# Sheet1.net
KiCad netlist of a schematic drawn in Altium Designer
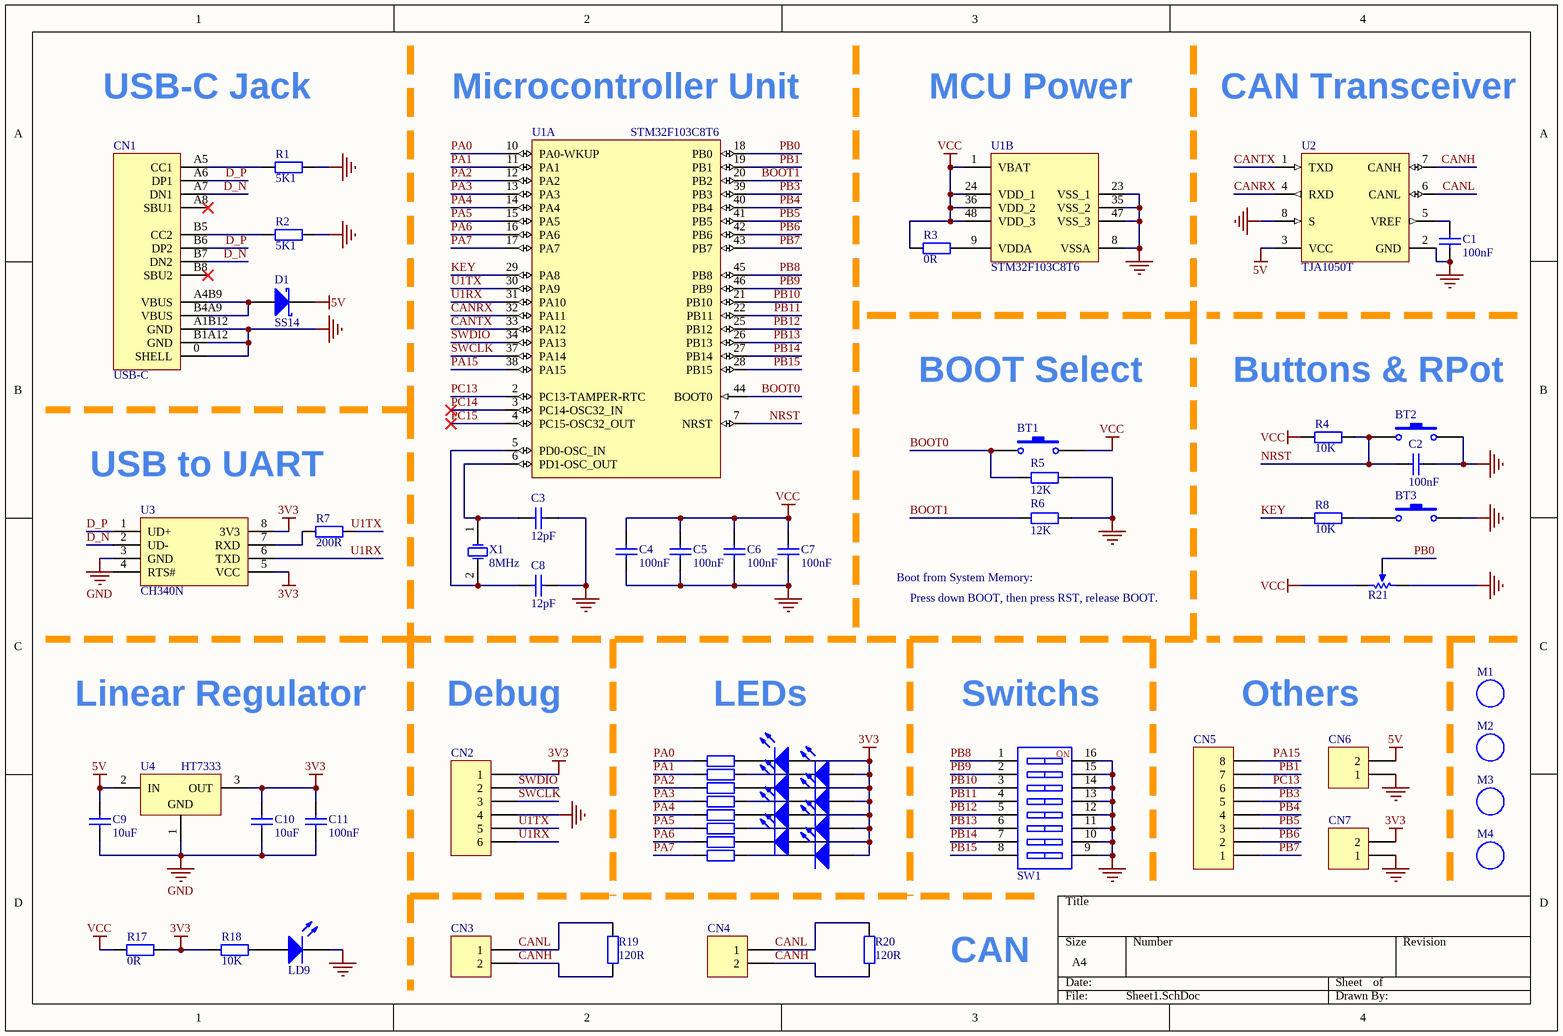
[diagram p0: Sheet1.SchDoc]

(export (version "E")
  (design (tool "Eeschema 10.0.6"))
  (components
    (comp (ref "BT1")
      (value "SW-PB")
      (footprint "TSW SMD-3*4*2.5")
      (description "Switch")
      (fields (field (name "PUBLISHER") "Altium Limited"))
      (libsource (lib "Miscellaneous Devices") (part "SW-PB"))
    )
    (comp (ref "BT2")
      (value "SW-PB")
      (footprint "TSW SMD-3*6*2.5")
      (description "Switch")
      (fields (field (name "PUBLISHER") "Altium Limited"))
      (libsource (lib "Miscellaneous Devices") (part "SW-PB"))
    )
    (comp (ref "BT3")
      (value "SW-PB")
      (footprint "TSW SMD-3*6*2.5")
      (description "Switch")
      (fields (field (name "PUBLISHER") "Altium Limited"))
      (libsource (lib "Miscellaneous Devices") (part "SW-PB"))
    )
    (comp (ref "C1")
      (value "100nF")
      (footprint "C 0603")
      (description "Capacitor")
      (fields (field (name "Comment") "Cap") (field (name "PUBLISHER") "Altium Limited"))
      (libsource (lib "Miscellaneous Devices") (part "Cap"))
    )
    (comp (ref "C2")
      (value "100nF")
      (footprint "C 0603")
      (description "Capacitor")
      (fields (field (name "Comment") "Cap") (field (name "PUBLISHER") "Altium Limited"))
      (libsource (lib "Miscellaneous Devices") (part "Cap"))
    )
    (comp (ref "C3")
      (value "12pF")
      (footprint "C 0603")
      (description "Capacitor")
      (fields (field (name "Comment") "Cap") (field (name "PUBLISHER") "Altium Limited"))
      (libsource (lib "Miscellaneous Devices") (part "Cap"))
    )
    (comp (ref "C4")
      (value "100nF")
      (footprint "C 0603")
      (description "Capacitor")
      (fields (field (name "Comment") "Cap") (field (name "PUBLISHER") "Altium Limited"))
      (libsource (lib "Miscellaneous Devices") (part "Cap"))
    )
    (comp (ref "C5")
      (value "100nF")
      (footprint "C 0603")
      (description "Capacitor")
      (fields (field (name "Comment") "Cap") (field (name "PUBLISHER") "Altium Limited"))
      (libsource (lib "Miscellaneous Devices") (part "Cap"))
    )
    (comp (ref "C6")
      (value "100nF")
      (footprint "C 0603")
      (description "Capacitor")
      (fields (field (name "Comment") "Cap") (field (name "PUBLISHER") "Altium Limited"))
      (libsource (lib "Miscellaneous Devices") (part "Cap"))
    )
    (comp (ref "C7")
      (value "100nF")
      (footprint "C 0603")
      (description "Capacitor")
      (fields (field (name "Comment") "Cap") (field (name "PUBLISHER") "Altium Limited"))
      (libsource (lib "Miscellaneous Devices") (part "Cap"))
    )
    (comp (ref "C8")
      (value "12pF")
      (footprint "C 0603")
      (description "Capacitor")
      (fields (field (name "Comment") "Cap") (field (name "PUBLISHER") "Altium Limited"))
      (libsource (lib "Miscellaneous Devices") (part "Cap"))
    )
    (comp (ref "C9")
      (value "10uF")
      (footprint "C 0603")
      (description "Capacitor")
      (fields (field (name "Comment") "Cap") (field (name "PUBLISHER") "Altium Limited"))
      (libsource (lib "Miscellaneous Devices") (part "Cap"))
    )
    (comp (ref "C10")
      (value "10uF")
      (footprint "C 0603")
      (description "Capacitor")
      (fields (field (name "Comment") "Cap") (field (name "PUBLISHER") "Altium Limited"))
      (libsource (lib "Miscellaneous Devices") (part "Cap"))
    )
    (comp (ref "C11")
      (value "100nF")
      (footprint "C 0603")
      (description "Capacitor")
      (fields (field (name "Comment") "Cap") (field (name "PUBLISHER") "Altium Limited"))
      (libsource (lib "Miscellaneous Devices") (part "Cap"))
    )
    (comp (ref "CN1")
      (value "USB-C")
      (footprint "USB-C/S_C_BCP16")
      (description "USB-C型母接口")
      (libsource (lib "接口类") (part "USB-C/16-Pin"))
    )
    (comp (ref "CN2")
      (value "Header 6")
      (footprint "XH2.54-6P_H")
      (description "Header, 6-Pin")
      (fields (field (name "PUBLISHER") "Altium Limited"))
      (libsource (lib "Miscellaneous Connectors") (part "Header 6"))
    )
    (comp (ref "CN3")
      (value "Header 2")
      (footprint "XH2.54-2P_H")
      (description "Header, 2-Pin")
      (fields (field (name "PUBLISHER") "Altium Limited"))
      (libsource (lib "Miscellaneous Connectors") (part "Header 2"))
    )
    (comp (ref "CN4")
      (value "Header 2")
      (footprint "XH2.54-2P_H")
      (description "Header, 2-Pin")
      (fields (field (name "PUBLISHER") "Altium Limited"))
      (libsource (lib "Miscellaneous Connectors") (part "Header 2"))
    )
    (comp (ref "CN5")
      (value "Header 8")
      (footprint "HDR1X8")
      (description "Header, 8-Pin")
      (fields (field (name "PUBLISHER") "Altium Limited"))
      (libsource (lib "Miscellaneous Connectors") (part "Header 8"))
    )
    (comp (ref "CN6")
      (value "Header 2")
      (footprint "HDR1X2")
      (description "Header, 2-Pin")
      (fields (field (name "PUBLISHER") "Altium Limited"))
      (libsource (lib "") (part "Header 2_1"))
    )
    (comp (ref "CN7")
      (value "Header 2")
      (footprint "HDR1X2")
      (description "Header, 2-Pin")
      (fields (field (name "PUBLISHER") "Altium Limited"))
      (libsource (lib "") (part "Header 2_1"))
    )
    (comp (ref "D1")
      (value "SS14")
      (footprint "SMA")
      (description "Schottky Diode")
      (fields (field (name "PUBLISHER") "Altium Limited"))
      (libsource (lib "Miscellaneous Devices") (part "D Schottky"))
    )
    (comp (ref "LD1")
      (value "150080SS75000")
      (footprint "0805_A")
      (description "SMD mono-color Chip LED, WL-SMCW, Super Red")
      (fields (field (name "MANUFACTURER") "Wuerth Elektronik"))
      (libsource (lib "Altium Content Vault") (part "WE-LED_K1A2-2"))
    )
    (comp (ref "LD2")
      (value "150080SS75000")
      (footprint "0805_A")
      (description "SMD mono-color Chip LED, WL-SMCW, Super Red")
      (fields (field (name "MANUFACTURER") "Wuerth Elektronik"))
      (libsource (lib "Altium Content Vault") (part "WE-LED_K1A2-2"))
    )
    (comp (ref "LD3")
      (value "150080SS75000")
      (footprint "0805_A")
      (description "SMD mono-color Chip LED, WL-SMCW, Super Red")
      (fields (field (name "MANUFACTURER") "Wuerth Elektronik"))
      (libsource (lib "Altium Content Vault") (part "WE-LED_K1A2-2"))
    )
    (comp (ref "LD4")
      (value "150080SS75000")
      (footprint "0805_A")
      (description "SMD mono-color Chip LED, WL-SMCW, Super Red")
      (fields (field (name "MANUFACTURER") "Wuerth Elektronik"))
      (libsource (lib "Altium Content Vault") (part "WE-LED_K1A2-2"))
    )
    (comp (ref "LD5")
      (value "150080SS75000")
      (footprint "0805_A")
      (description "SMD mono-color Chip LED, WL-SMCW, Super Red")
      (fields (field (name "MANUFACTURER") "Wuerth Elektronik"))
      (libsource (lib "Altium Content Vault") (part "WE-LED_K1A2-2"))
    )
    (comp (ref "LD6")
      (value "150080SS75000")
      (footprint "0805_A")
      (description "SMD mono-color Chip LED, WL-SMCW, Super Red")
      (fields (field (name "MANUFACTURER") "Wuerth Elektronik"))
      (libsource (lib "Altium Content Vault") (part "WE-LED_K1A2-2"))
    )
    (comp (ref "LD7")
      (value "150080SS75000")
      (footprint "0805_A")
      (description "SMD mono-color Chip LED, WL-SMCW, Super Red")
      (fields (field (name "MANUFACTURER") "Wuerth Elektronik"))
      (libsource (lib "Altium Content Vault") (part "WE-LED_K1A2-2"))
    )
    (comp (ref "LD8")
      (value "150080SS75000")
      (footprint "0805_A")
      (description "SMD mono-color Chip LED, WL-SMCW, Super Red")
      (fields (field (name "MANUFACTURER") "Wuerth Elektronik"))
      (libsource (lib "Altium Content Vault") (part "WE-LED_K1A2-2"))
    )
    (comp (ref "LD9")
      (value "150080SS75000")
      (footprint "0805_A")
      (description "SMD mono-color Chip LED, WL-SMCW, Super Red")
      (fields (field (name "MANUFACTURER") "Wuerth Elektronik"))
      (libsource (lib "Altium Content Vault") (part "WE-LED_K1A2-2"))
    )
    (comp (ref "M1")
      (value "M3")
      (footprint "M3 125X200")
      (description "铜柱孔")
      (fields (field (name "版权归属") "源创客"))
      (libsource (lib "未分类器件") (part "M3"))
    )
    (comp (ref "M2")
      (value "M3")
      (footprint "M3 125X200")
      (description "铜柱孔")
      (fields (field (name "版权归属") "源创客"))
      (libsource (lib "未分类器件") (part "M3"))
    )
    (comp (ref "M3")
      (value "M3")
      (footprint "M3 125X200")
      (description "铜柱孔")
      (fields (field (name "版权归属") "源创客"))
      (libsource (lib "未分类器件") (part "M3"))
    )
    (comp (ref "M4")
      (value "M3")
      (footprint "M3 125X200")
      (description "铜柱孔")
      (fields (field (name "版权归属") "源创客"))
      (libsource (lib "未分类器件") (part "M3"))
    )
    (comp (ref "R1")
      (value "5K1")
      (footprint "R 0805")
      (description "Resistor")
      (fields (field (name "Comment") "Res2") (field (name "PUBLISHER") "Altium Limited"))
      (libsource (lib "Miscellaneous Devices") (part "Res2"))
    )
    (comp (ref "R2")
      (value "5K1")
      (footprint "R 0805")
      (description "Resistor")
      (fields (field (name "Comment") "Res2") (field (name "PUBLISHER") "Altium Limited"))
      (libsource (lib "Miscellaneous Devices") (part "Res2"))
    )
    (comp (ref "R3")
      (value "0R")
      (footprint "R 0805")
      (description "Resistor")
      (fields (field (name "Comment") "Res2") (field (name "PUBLISHER") "Altium Limited"))
      (libsource (lib "Miscellaneous Devices") (part "Res2"))
    )
    (comp (ref "R4")
      (value "10K")
      (footprint "R 0805")
      (description "Resistor")
      (fields (field (name "Comment") "Res2") (field (name "PUBLISHER") "Altium Limited"))
      (libsource (lib "Miscellaneous Devices") (part "Res2"))
    )
    (comp (ref "R5")
      (value "12K")
      (footprint "R 0805")
      (description "贴片电阻")
      (fields (field (name "版权归属") "源创客"))
      (libsource (lib "电阻-电容-电感") (part "R"))
    )
    (comp (ref "R6")
      (value "12K")
      (footprint "R 0805")
      (description "贴片电阻")
      (fields (field (name "版权归属") "源创客"))
      (libsource (lib "电阻-电容-电感") (part "R"))
    )
    (comp (ref "R7")
      (value "200R")
      (footprint "R 0805")
      (description "Resistor")
      (fields (field (name "Comment") "Res2") (field (name "PUBLISHER") "Altium Limited"))
      (libsource (lib "Miscellaneous Devices") (part "Res2"))
    )
    (comp (ref "R8")
      (value "10K")
      (footprint "R 0805")
      (description "Resistor")
      (fields (field (name "Comment") "Res2") (field (name "PUBLISHER") "Altium Limited"))
      (libsource (lib "Miscellaneous Devices") (part "Res2"))
    )
    (comp (ref "R9")
      (value "Res2")
      (footprint "R 0805")
      (description "Resistor")
      (fields (field (name "PUBLISHER") "Altium Limited"))
      (libsource (lib "") (part "Res2_1"))
    )
    (comp (ref "R10")
      (value "Res2")
      (footprint "R 0805")
      (description "Resistor")
      (fields (field (name "PUBLISHER") "Altium Limited"))
      (libsource (lib "") (part "Res2_1"))
    )
    (comp (ref "R11")
      (value "Res2")
      (footprint "R 0805")
      (description "Resistor")
      (fields (field (name "PUBLISHER") "Altium Limited"))
      (libsource (lib "") (part "Res2_1"))
    )
    (comp (ref "R12")
      (value "Res2")
      (footprint "R 0805")
      (description "Resistor")
      (fields (field (name "PUBLISHER") "Altium Limited"))
      (libsource (lib "") (part "Res2_1"))
    )
    (comp (ref "R13")
      (value "Res2")
      (footprint "R 0805")
      (description "Resistor")
      (fields (field (name "PUBLISHER") "Altium Limited"))
      (libsource (lib "") (part "Res2_1"))
    )
    (comp (ref "R14")
      (value "Res2")
      (footprint "R 0805")
      (description "Resistor")
      (fields (field (name "PUBLISHER") "Altium Limited"))
      (libsource (lib "") (part "Res2_1"))
    )
    (comp (ref "R15")
      (value "Res2")
      (footprint "R 0805")
      (description "Resistor")
      (fields (field (name "PUBLISHER") "Altium Limited"))
      (libsource (lib "") (part "Res2_1"))
    )
    (comp (ref "R16")
      (value "Res2")
      (footprint "R 0805")
      (description "Resistor")
      (fields (field (name "PUBLISHER") "Altium Limited"))
      (libsource (lib "") (part "Res2_1"))
    )
    (comp (ref "R17")
      (value "0R")
      (footprint "R 0805")
      (description "Resistor")
      (fields (field (name "Comment") "Res2") (field (name "PUBLISHER") "Altium Limited"))
      (libsource (lib "") (part "Res2_1"))
    )
    (comp (ref "R18")
      (value "10K")
      (footprint "R 0805")
      (description "Resistor")
      (fields (field (name "Comment") "Res2") (field (name "PUBLISHER") "Altium Limited"))
      (libsource (lib "") (part "Res2_1"))
    )
    (comp (ref "R19")
      (value "120R")
      (footprint "R 0805")
      (description "Resistor")
      (fields (field (name "Comment") "Res2") (field (name "PUBLISHER") "Altium Limited"))
      (libsource (lib "") (part "Res2_2"))
    )
    (comp (ref "R20")
      (value "120R")
      (footprint "R 0805")
      (description "Resistor")
      (fields (field (name "Comment") "Res2") (field (name "PUBLISHER") "Altium Limited"))
      (libsource (lib "") (part "Res2_2"))
    )
    (comp (ref "R21")
      (value "RPot")
      (footprint "RM065")
      (description "Potentiometer")
      (fields (field (name "PUBLISHER") "Altium Limited"))
      (libsource (lib "Miscellaneous Devices") (part "RPot"))
    )
    (comp (ref "SW1")
      (value "CSW-8P")
      (footprint "CSW DIP-8P")
      (description "8路编码开关")
      (fields (field (name "版权归属") "源创客"))
      (libsource (lib "按键-开关") (part "CSW-8P"))
    )
    (comp (ref "U1")
      (value "STM32F103C8T6")
      (footprint "STM-LQFP48_L")
      (libsource (lib "Altium Content Vault") (part "MC-ARM-STM32F103X8_B-SQ48"))
    )
    (comp (ref "U2")
      (value "TJA1050T")
      (footprint "NXP-SOT96-1_M")
      (fields (field (name "MANUFACTURER") "NXP Semiconductors"))
      (libsource (lib "Altium Content Vault") (part "NXP-TJA1050-8"))
    )
    (comp (ref "U3") (value "CH340N") (footprint "SOP8_N") (libsource (lib "Misaka") (part "CH340N")))
    (comp (ref "U4")
      (value "HT7333")
      (footprint "SOT89_N")
      (description "Low Power Consumption LDO, Output Voltage 3.3V, SOT89 Pkg")
      (libsource (lib "Altium Content Vault") (part "PM-REG-HT73XX-IL3"))
    )
    (comp (ref "X1")
      (value "8MHz")
      (footprint "ABRA-ABM3-2_V")
      (description "Miniature Ceramic Crystal, 8 MHz, -40 to 85 degC, 2-Pin SMD, RoHS, Tape and Reel")
      (fields (field (name "MANUFACTURER") "ABRACON") (field (name "TOLERANCE") "20PPM"))
      (libsource (lib "Altium Content Vault") (part "XTAL_1-2-2"))
    )
  )
  (nets
    (net (code "1") (name "/BOOT0") (class "Default")
      (node (ref "BT1") (pin "2") (pinfunction "2_2") (pintype "passive"))
      (node (ref "R5") (pin "1") (pinfunction "1_1") (pintype "passive"))
      (node (ref "U1") (pin "44") (pinfunction "BOOT0_44") (pintype "input"))
    )
    (net (code "2") (name "/BOOT1") (class "Default")
      (node (ref "R6") (pin "1") (pinfunction "1_1") (pintype "passive"))
      (node (ref "U1") (pin "20") (pinfunction "PB2_20") (pintype "bidirectional"))
    )
    (net (code "3") (name "/CANH") (class "Default")
      (node (ref "CN3") (pin "2") (pinfunction "2_2") (pintype "passive"))
      (node (ref "CN4") (pin "2") (pinfunction "2_2") (pintype "passive"))
      (node (ref "R19") (pin "1") (pinfunction "1_1") (pintype "passive"))
      (node (ref "R20") (pin "1") (pinfunction "1_1") (pintype "passive"))
      (node (ref "U2") (pin "7") (pinfunction "CANH_7") (pintype "bidirectional"))
    )
    (net (code "4") (name "/CANL") (class "Default")
      (node (ref "CN3") (pin "1") (pinfunction "1_1") (pintype "passive"))
      (node (ref "CN4") (pin "1") (pinfunction "1_1") (pintype "passive"))
      (node (ref "R19") (pin "2") (pinfunction "2_2") (pintype "passive"))
      (node (ref "R20") (pin "2") (pinfunction "2_2") (pintype "passive"))
      (node (ref "U2") (pin "6") (pinfunction "CANL_6") (pintype "bidirectional"))
    )
    (net (code "5") (name "/CANRX") (class "Default")
      (node (ref "U1") (pin "32") (pinfunction "PA11_32") (pintype "bidirectional"))
      (node (ref "U2") (pin "4") (pinfunction "RXD_4") (pintype "output"))
    )
    (net (code "6") (name "/CANTX") (class "Default")
      (node (ref "U1") (pin "33") (pinfunction "PA12_33") (pintype "bidirectional"))
      (node (ref "U2") (pin "1") (pinfunction "TXD_1") (pintype "input"))
    )
    (net (code "7") (name "/D_N") (class "Default")
      (node (ref "CN1") (pin "A7") (pinfunction "DN1_A7") (pintype "passive"))
      (node (ref "CN1") (pin "B7") (pinfunction "DN2_B7") (pintype "passive"))
      (node (ref "U3") (pin "2") (pinfunction "UD-_2") (pintype "passive"))
    )
    (net (code "8") (name "/D_P") (class "Default")
      (node (ref "CN1") (pin "A6") (pinfunction "DP1_A6") (pintype "passive"))
      (node (ref "CN1") (pin "B6") (pinfunction "DP2_B6") (pintype "passive"))
      (node (ref "U3") (pin "1") (pinfunction "UD+_1") (pintype "passive"))
    )
    (net (code "9") (name "/KEY") (class "Default")
      (node (ref "R8") (pin "1") (pinfunction "1_1") (pintype "passive"))
      (node (ref "U1") (pin "29") (pinfunction "PA8_29") (pintype "bidirectional"))
    )
    (net (code "10") (name "/NRST") (class "Default")
      (node (ref "BT2") (pin "1") (pinfunction "1_1") (pintype "passive"))
      (node (ref "C2") (pin "2") (pinfunction "2_2") (pintype "passive"))
      (node (ref "R4") (pin "2") (pinfunction "2_2") (pintype "passive"))
      (node (ref "U1") (pin "7") (pinfunction "NRST_7") (pintype "bidirectional"))
    )
    (net (code "11") (name "/PA0") (class "Default")
      (node (ref "R9") (pin "2") (pinfunction "2_2") (pintype "passive"))
      (node (ref "U1") (pin "10") (pinfunction "PA0-WKUP_10") (pintype "bidirectional"))
    )
    (net (code "12") (name "/PA1") (class "Default")
      (node (ref "R10") (pin "2") (pinfunction "2_2") (pintype "passive"))
      (node (ref "U1") (pin "11") (pinfunction "PA1_11") (pintype "bidirectional"))
    )
    (net (code "13") (name "/PA2") (class "Default")
      (node (ref "R11") (pin "2") (pinfunction "2_2") (pintype "passive"))
      (node (ref "U1") (pin "12") (pinfunction "PA2_12") (pintype "bidirectional"))
    )
    (net (code "14") (name "/PA3") (class "Default")
      (node (ref "R12") (pin "2") (pinfunction "2_2") (pintype "passive"))
      (node (ref "U1") (pin "13") (pinfunction "PA3_13") (pintype "bidirectional"))
    )
    (net (code "15") (name "/PA4") (class "Default")
      (node (ref "R13") (pin "2") (pinfunction "2_2") (pintype "passive"))
      (node (ref "U1") (pin "14") (pinfunction "PA4_14") (pintype "bidirectional"))
    )
    (net (code "16") (name "/PA5") (class "Default")
      (node (ref "R14") (pin "2") (pinfunction "2_2") (pintype "passive"))
      (node (ref "U1") (pin "15") (pinfunction "PA5_15") (pintype "bidirectional"))
    )
    (net (code "17") (name "/PA6") (class "Default")
      (node (ref "R15") (pin "2") (pinfunction "2_2") (pintype "passive"))
      (node (ref "U1") (pin "16") (pinfunction "PA6_16") (pintype "bidirectional"))
    )
    (net (code "18") (name "/PA7") (class "Default")
      (node (ref "R16") (pin "2") (pinfunction "2_2") (pintype "passive"))
      (node (ref "U1") (pin "17") (pinfunction "PA7_17") (pintype "bidirectional"))
    )
    (net (code "19") (name "/PA15") (class "Default")
      (node (ref "CN5") (pin "8") (pinfunction "8_8") (pintype "passive"))
      (node (ref "U1") (pin "38") (pinfunction "PA15_38") (pintype "bidirectional"))
    )
    (net (code "20") (name "/PB0") (class "Default")
      (node (ref "R21") (pin "3") (pinfunction "TAP_3") (pintype "passive"))
      (node (ref "U1") (pin "18") (pinfunction "PB0_18") (pintype "bidirectional"))
    )
    (net (code "21") (name "/PB1") (class "Default")
      (node (ref "CN5") (pin "7") (pinfunction "7_7") (pintype "passive"))
      (node (ref "U1") (pin "19") (pinfunction "PB1_19") (pintype "bidirectional"))
    )
    (net (code "22") (name "/PB3") (class "Default")
      (node (ref "CN5") (pin "5") (pinfunction "5_5") (pintype "passive"))
      (node (ref "U1") (pin "39") (pinfunction "PB3_39") (pintype "bidirectional"))
    )
    (net (code "23") (name "/PB4") (class "Default")
      (node (ref "CN5") (pin "4") (pinfunction "4_4") (pintype "passive"))
      (node (ref "U1") (pin "40") (pinfunction "PB4_40") (pintype "bidirectional"))
    )
    (net (code "24") (name "/PB5") (class "Default")
      (node (ref "CN5") (pin "3") (pinfunction "3_3") (pintype "passive"))
      (node (ref "U1") (pin "41") (pinfunction "PB5_41") (pintype "bidirectional"))
    )
    (net (code "25") (name "/PB6") (class "Default")
      (node (ref "CN5") (pin "2") (pinfunction "2_2") (pintype "passive"))
      (node (ref "U1") (pin "42") (pinfunction "PB6_42") (pintype "bidirectional"))
    )
    (net (code "26") (name "/PB7") (class "Default")
      (node (ref "CN5") (pin "1") (pinfunction "1_1") (pintype "passive"))
      (node (ref "U1") (pin "43") (pinfunction "PB7_43") (pintype "bidirectional"))
    )
    (net (code "27") (name "/PB8") (class "Default")
      (node (ref "SW1") (pin "1") (pinfunction "1_1") (pintype "passive"))
      (node (ref "U1") (pin "45") (pinfunction "PB8_45") (pintype "bidirectional"))
    )
    (net (code "28") (name "/PB9") (class "Default")
      (node (ref "SW1") (pin "2") (pinfunction "2_2") (pintype "passive"))
      (node (ref "U1") (pin "46") (pinfunction "PB9_46") (pintype "bidirectional"))
    )
    (net (code "29") (name "/PB10") (class "Default")
      (node (ref "SW1") (pin "3") (pinfunction "3_3") (pintype "passive"))
      (node (ref "U1") (pin "21") (pinfunction "PB10_21") (pintype "bidirectional"))
    )
    (net (code "30") (name "/PB11") (class "Default")
      (node (ref "SW1") (pin "4") (pinfunction "4_4") (pintype "passive"))
      (node (ref "U1") (pin "22") (pinfunction "PB11_22") (pintype "bidirectional"))
    )
    (net (code "31") (name "/PB12") (class "Default")
      (node (ref "SW1") (pin "5") (pinfunction "5_5") (pintype "passive"))
      (node (ref "U1") (pin "25") (pinfunction "PB12_25") (pintype "bidirectional"))
    )
    (net (code "32") (name "/PB13") (class "Default")
      (node (ref "SW1") (pin "6") (pinfunction "6_6") (pintype "passive"))
      (node (ref "U1") (pin "26") (pinfunction "PB13_26") (pintype "bidirectional"))
    )
    (net (code "33") (name "/PB14") (class "Default")
      (node (ref "SW1") (pin "7") (pinfunction "7_7") (pintype "passive"))
      (node (ref "U1") (pin "27") (pinfunction "PB14_27") (pintype "bidirectional"))
    )
    (net (code "34") (name "/PB15") (class "Default")
      (node (ref "SW1") (pin "8") (pinfunction "8_8") (pintype "passive"))
      (node (ref "U1") (pin "28") (pinfunction "PB15_28") (pintype "bidirectional"))
    )
    (net (code "35") (name "/PC13") (class "Default")
      (node (ref "CN5") (pin "6") (pinfunction "6_6") (pintype "passive"))
      (node (ref "U1") (pin "2") (pinfunction "PC13-TAMPER-RTC_2") (pintype "bidirectional"))
    )
    (net (code "36") (name "/PC14") (class "Default")
      (node (ref "U1") (pin "3") (pinfunction "PC14-OSC32_IN_3") (pintype "bidirectional+no_connect"))
    )
    (net (code "37") (name "/PC15") (class "Default")
      (node (ref "U1") (pin "4") (pinfunction "PC15-OSC32_OUT_4") (pintype "bidirectional+no_connect"))
    )
    (net (code "38") (name "/SWCLK") (class "Default")
      (node (ref "CN2") (pin "3") (pinfunction "3_3") (pintype "passive"))
      (node (ref "U1") (pin "37") (pinfunction "PA14_37") (pintype "bidirectional"))
    )
    (net (code "39") (name "/SWDIO") (class "Default")
      (node (ref "CN2") (pin "2") (pinfunction "2_2") (pintype "passive"))
      (node (ref "U1") (pin "34") (pinfunction "PA13_34") (pintype "bidirectional"))
    )
    (net (code "40") (name "/U1RX") (class "Default")
      (node (ref "CN2") (pin "6") (pinfunction "6_6") (pintype "passive"))
      (node (ref "U1") (pin "31") (pinfunction "PA10_31") (pintype "bidirectional"))
      (node (ref "U3") (pin "6") (pinfunction "TXD_6") (pintype "passive"))
    )
    (net (code "41") (name "/U1TX") (class "Default")
      (node (ref "CN2") (pin "5") (pinfunction "5_5") (pintype "passive"))
      (node (ref "R7") (pin "2") (pinfunction "2_2") (pintype "passive"))
      (node (ref "U1") (pin "30") (pinfunction "PA9_30") (pintype "bidirectional"))
    )
    (net (code "42") (name "3V3") (class "Default")
      (node (ref "C10") (pin "1") (pinfunction "1_1") (pintype "passive"))
      (node (ref "C11") (pin "1") (pinfunction "1_1") (pintype "passive"))
      (node (ref "CN2") (pin "1") (pinfunction "1_1") (pintype "passive"))
      (node (ref "CN7") (pin "2") (pinfunction "2_2") (pintype "passive"))
      (node (ref "LD1") (pin "2") (pinfunction "A_2") (pintype "passive"))
      (node (ref "LD2") (pin "2") (pinfunction "A_2") (pintype "passive"))
      (node (ref "LD3") (pin "2") (pinfunction "A_2") (pintype "passive"))
      (node (ref "LD4") (pin "2") (pinfunction "A_2") (pintype "passive"))
      (node (ref "LD5") (pin "2") (pinfunction "A_2") (pintype "passive"))
      (node (ref "LD6") (pin "2") (pinfunction "A_2") (pintype "passive"))
      (node (ref "LD7") (pin "2") (pinfunction "A_2") (pintype "passive"))
      (node (ref "LD8") (pin "2") (pinfunction "A_2") (pintype "passive"))
      (node (ref "R17") (pin "1") (pinfunction "1_1") (pintype "passive"))
      (node (ref "R18") (pin "2") (pinfunction "2_2") (pintype "passive"))
      (node (ref "U3") (pin "5") (pinfunction "VCC_5") (pintype "passive"))
      (node (ref "U3") (pin "8") (pinfunction "3V3_8") (pintype "passive"))
      (node (ref "U4") (pin "3") (pinfunction "OUT_3") (pintype "power_in"))
    )
    (net (code "43") (name "5V") (class "Default")
      (node (ref "C9") (pin "1") (pinfunction "1_1") (pintype "passive"))
      (node (ref "CN6") (pin "2") (pinfunction "2_2") (pintype "passive"))
      (node (ref "D1") (pin "2") (pinfunction "K_2") (pintype "passive"))
      (node (ref "U2") (pin "3") (pinfunction "VCC_3") (pintype "power_in"))
      (node (ref "U4") (pin "2") (pinfunction "IN_2") (pintype "power_in"))
    )
    (net (code "44") (name "GND") (class "Default")
      (node (ref "BT2") (pin "2") (pinfunction "2_2") (pintype "passive"))
      (node (ref "BT3") (pin "2") (pinfunction "2_2") (pintype "passive"))
      (node (ref "C1") (pin "2") (pinfunction "2_2") (pintype "passive"))
      (node (ref "C10") (pin "2") (pinfunction "2_2") (pintype "passive"))
      (node (ref "C11") (pin "2") (pinfunction "2_2") (pintype "passive"))
      (node (ref "C2") (pin "1") (pinfunction "1_1") (pintype "passive"))
      (node (ref "C3") (pin "2") (pinfunction "2_2") (pintype "passive"))
      (node (ref "C4") (pin "1") (pinfunction "1_1") (pintype "passive"))
      (node (ref "C5") (pin "1") (pinfunction "1_1") (pintype "passive"))
      (node (ref "C6") (pin "1") (pinfunction "1_1") (pintype "passive"))
      (node (ref "C7") (pin "1") (pinfunction "1_1") (pintype "passive"))
      (node (ref "C8") (pin "2") (pinfunction "2_2") (pintype "passive"))
      (node (ref "C9") (pin "2") (pinfunction "2_2") (pintype "passive"))
      (node (ref "CN1") (pin "0") (pinfunction "SHELL_0") (pintype "passive"))
      (node (ref "CN1") (pin "A1B12") (pinfunction "GND_A1B12") (pintype "passive"))
      (node (ref "CN1") (pin "B1A12") (pinfunction "GND_B1A12") (pintype "passive"))
      (node (ref "CN2") (pin "4") (pinfunction "4_4") (pintype "passive"))
      (node (ref "CN6") (pin "1") (pinfunction "1_1") (pintype "passive"))
      (node (ref "CN7") (pin "1") (pinfunction "1_1") (pintype "passive"))
      (node (ref "LD9") (pin "1") (pinfunction "K_1") (pintype "passive"))
      (node (ref "R1") (pin "2") (pinfunction "2_2") (pintype "passive"))
      (node (ref "R2") (pin "2") (pinfunction "2_2") (pintype "passive"))
      (node (ref "R21") (pin "2") (pinfunction "BOT_2") (pintype "passive"))
      (node (ref "R5") (pin "2") (pinfunction "2_2") (pintype "passive"))
      (node (ref "R6") (pin "2") (pinfunction "2_2") (pintype "passive"))
      (node (ref "SW1") (pin "10") (pinfunction "10_10") (pintype "passive"))
      (node (ref "SW1") (pin "11") (pinfunction "11_11") (pintype "passive"))
      (node (ref "SW1") (pin "12") (pinfunction "12_12") (pintype "passive"))
      (node (ref "SW1") (pin "13") (pinfunction "13_13") (pintype "passive"))
      (node (ref "SW1") (pin "14") (pinfunction "14_14") (pintype "passive"))
      (node (ref "SW1") (pin "15") (pinfunction "15_15") (pintype "passive"))
      (node (ref "SW1") (pin "16") (pinfunction "16_16") (pintype "passive"))
      (node (ref "SW1") (pin "9") (pinfunction "9_9") (pintype "passive"))
      (node (ref "U1") (pin "23") (pinfunction "VSS_1_23") (pintype "power_in"))
      (node (ref "U1") (pin "35") (pinfunction "VSS_2_35") (pintype "power_in"))
      (node (ref "U1") (pin "47") (pinfunction "VSS_3_47") (pintype "power_in"))
      (node (ref "U1") (pin "8") (pinfunction "VSSA_8") (pintype "power_in"))
      (node (ref "U2") (pin "2") (pinfunction "GND_2") (pintype "power_in"))
      (node (ref "U2") (pin "8") (pinfunction "S_8") (pintype "input"))
      (node (ref "U3") (pin "3") (pinfunction "GND_3") (pintype "passive"))
      (node (ref "U4") (pin "1") (pinfunction "GND_1") (pintype "power_in"))
    )
    (net (code "45") (name "Net-(BT3-Pad1)") (class "Default")
      (node (ref "BT3") (pin "1") (pinfunction "1_1") (pintype "passive"))
      (node (ref "R8") (pin "2") (pinfunction "2_2") (pintype "passive"))
    )
    (net (code "46") (name "Net-(CN1-CC1)") (class "Default")
      (node (ref "CN1") (pin "A5") (pinfunction "CC1_A5") (pintype "passive"))
      (node (ref "R1") (pin "1") (pinfunction "1_1") (pintype "passive"))
    )
    (net (code "47") (name "Net-(CN1-CC2)") (class "Default")
      (node (ref "CN1") (pin "B5") (pinfunction "CC2_B5") (pintype "passive"))
      (node (ref "R2") (pin "1") (pinfunction "1_1") (pintype "passive"))
    )
    (net (code "48") (name "Net-(D1-A)") (class "Default")
      (node (ref "CN1") (pin "A4B9") (pinfunction "VBUS_A4B9") (pintype "passive"))
      (node (ref "CN1") (pin "B4A9") (pinfunction "VBUS_B4A9") (pintype "passive"))
      (node (ref "D1") (pin "1") (pinfunction "A_1") (pintype "passive"))
    )
    (net (code "49") (name "Net-(LD1-K)") (class "Default")
      (node (ref "LD1") (pin "1") (pinfunction "K_1") (pintype "passive"))
      (node (ref "R9") (pin "1") (pinfunction "1_1") (pintype "passive"))
    )
    (net (code "50") (name "Net-(LD2-K)") (class "Default")
      (node (ref "LD2") (pin "1") (pinfunction "K_1") (pintype "passive"))
      (node (ref "R10") (pin "1") (pinfunction "1_1") (pintype "passive"))
    )
    (net (code "51") (name "Net-(LD3-K)") (class "Default")
      (node (ref "LD3") (pin "1") (pinfunction "K_1") (pintype "passive"))
      (node (ref "R11") (pin "1") (pinfunction "1_1") (pintype "passive"))
    )
    (net (code "52") (name "Net-(LD4-K)") (class "Default")
      (node (ref "LD4") (pin "1") (pinfunction "K_1") (pintype "passive"))
      (node (ref "R12") (pin "1") (pinfunction "1_1") (pintype "passive"))
    )
    (net (code "53") (name "Net-(LD5-K)") (class "Default")
      (node (ref "LD5") (pin "1") (pinfunction "K_1") (pintype "passive"))
      (node (ref "R13") (pin "1") (pinfunction "1_1") (pintype "passive"))
    )
    (net (code "54") (name "Net-(LD6-K)") (class "Default")
      (node (ref "LD6") (pin "1") (pinfunction "K_1") (pintype "passive"))
      (node (ref "R14") (pin "1") (pinfunction "1_1") (pintype "passive"))
    )
    (net (code "55") (name "Net-(LD7-K)") (class "Default")
      (node (ref "LD7") (pin "1") (pinfunction "K_1") (pintype "passive"))
      (node (ref "R15") (pin "1") (pinfunction "1_1") (pintype "passive"))
    )
    (net (code "56") (name "Net-(LD8-K)") (class "Default")
      (node (ref "LD8") (pin "1") (pinfunction "K_1") (pintype "passive"))
      (node (ref "R16") (pin "1") (pinfunction "1_1") (pintype "passive"))
    )
    (net (code "57") (name "Net-(LD9-A)") (class "Default")
      (node (ref "LD9") (pin "2") (pinfunction "A_2") (pintype "passive"))
      (node (ref "R18") (pin "1") (pinfunction "1_1") (pintype "passive"))
    )
    (net (code "58") (name "Net-(U1A-PD0-OSC_IN)") (class "Default")
      (node (ref "C8") (pin "1") (pinfunction "1_1") (pintype "passive"))
      (node (ref "U1") (pin "5") (pinfunction "PD0-OSC_IN_5") (pintype "bidirectional"))
      (node (ref "X1") (pin "2") (pinfunction "X2_2") (pintype "passive"))
    )
    (net (code "59") (name "Net-(U1A-PD1-OSC_OUT)") (class "Default")
      (node (ref "C3") (pin "1") (pinfunction "1_1") (pintype "passive"))
      (node (ref "U1") (pin "6") (pinfunction "PD1-OSC_OUT_6") (pintype "bidirectional"))
      (node (ref "X1") (pin "1") (pinfunction "X1_1") (pintype "passive"))
    )
    (net (code "60") (name "Net-(U1B-VDDA)") (class "Default")
      (node (ref "R3") (pin "2") (pinfunction "2_2") (pintype "passive"))
      (node (ref "U1") (pin "9") (pinfunction "VDDA_9") (pintype "power_in"))
    )
    (net (code "61") (name "Net-(U2-VREF)") (class "Default")
      (node (ref "C1") (pin "1") (pinfunction "1_1") (pintype "passive"))
      (node (ref "U2") (pin "5") (pinfunction "VREF_5") (pintype "output"))
    )
    (net (code "62") (name "Net-(U3-RXD)") (class "Default")
      (node (ref "R7") (pin "1") (pinfunction "1_1") (pintype "passive"))
      (node (ref "U3") (pin "7") (pinfunction "RXD_7") (pintype "passive"))
    )
    (net (code "63") (name "VCC") (class "Default")
      (node (ref "BT1") (pin "1") (pinfunction "1_1") (pintype "passive"))
      (node (ref "C4") (pin "2") (pinfunction "2_2") (pintype "passive"))
      (node (ref "C5") (pin "2") (pinfunction "2_2") (pintype "passive"))
      (node (ref "C6") (pin "2") (pinfunction "2_2") (pintype "passive"))
      (node (ref "C7") (pin "2") (pinfunction "2_2") (pintype "passive"))
      (node (ref "R17") (pin "2") (pinfunction "2_2") (pintype "passive"))
      (node (ref "R21") (pin "1") (pinfunction "TOP_1") (pintype "passive"))
      (node (ref "R3") (pin "1") (pinfunction "1_1") (pintype "passive"))
      (node (ref "R4") (pin "1") (pinfunction "1_1") (pintype "passive"))
      (node (ref "U1") (pin "1") (pinfunction "VBAT_1") (pintype "power_in"))
      (node (ref "U1") (pin "24") (pinfunction "VDD_1_24") (pintype "power_in"))
      (node (ref "U1") (pin "36") (pinfunction "VDD_2_36") (pintype "power_in"))
      (node (ref "U1") (pin "48") (pinfunction "VDD_3_48") (pintype "power_in"))
    )
    (net (code "64") (name "unconnected-(CN1-SBU1-PadA8)") (class "Default")
      (node (ref "CN1") (pin "A8") (pinfunction "SBU1_A8") (pintype "passive+no_connect"))
    )
    (net (code "65") (name "unconnected-(CN1-SBU2-PadB8)") (class "Default")
      (node (ref "CN1") (pin "B8") (pinfunction "SBU2_B8") (pintype "passive+no_connect"))
    )
    (net (code "66") (name "unconnected-(U3-RTS#-Pad4)") (class "Default")
      (node (ref "U3") (pin "4") (pinfunction "RTS#_4") (pintype "passive"))
    )
  )
)
